# SPin.net
KiCad netlist of a schematic drawn in EAGLE
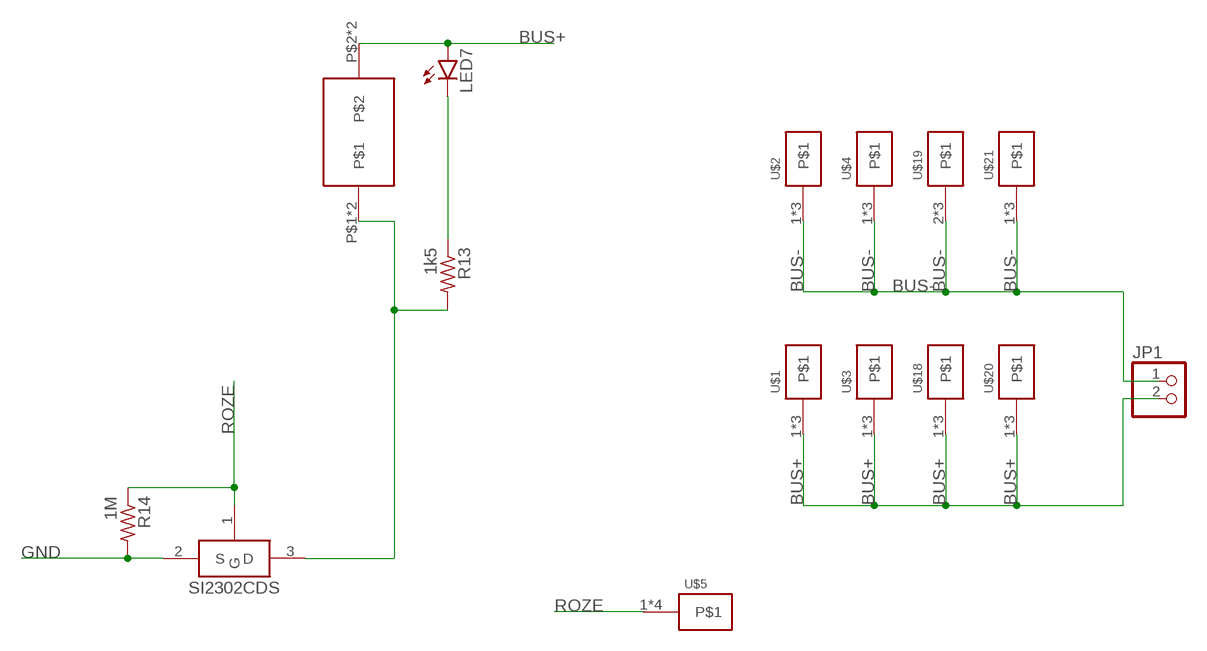
[diagram p0: schematic, sheet 1]

(export (version "E")
  (design (tool "Eeschema 10.0.6"))
  (components
    (comp (ref "JP1")
      (value "PINHD-1X2")
      (footprint "eagle-import:1X02")
      (libsource (lib "eagle-import") (part "PINHD-1X2"))
    )
    (comp (ref "LED7")
      (value "LEDCHIPLED_0603")
      (footprint "eagle-import:CHIPLED_0603")
      (libsource (lib "eagle-import") (part "LEDCHIPLED_0603"))
    )
    (comp (ref "R13")
      (value "1k5")
      (footprint "eagle-import:R0603")
      (libsource (lib "eagle-import") (part "R-US_R0603"))
    )
    (comp (ref "R14")
      (value "1M")
      (footprint "eagle-import:R0603")
      (libsource (lib "eagle-import") (part "R-US_R0603"))
    )
    (comp (ref "U$1")
      (value "KCONNECT3")
      (footprint "eagle-import:KCONNECT-3")
      (libsource (lib "eagle-import") (part "KCONNECT3"))
    )
    (comp (ref "U$2")
      (value "KCONNECT3")
      (footprint "eagle-import:KCONNECT-3")
      (libsource (lib "eagle-import") (part "KCONNECT3"))
    )
    (comp (ref "U$3")
      (value "KCONNECT4")
      (footprint "eagle-import:KCONNECT-4")
      (libsource (lib "eagle-import") (part "KCONNECT4"))
    )
    (comp (ref "U$4")
      (value "KCONNECT4")
      (footprint "eagle-import:KCONNECT-4")
      (libsource (lib "eagle-import") (part "KCONNECT4"))
    )
    (comp (ref "U$5")
      (value "KCONNECTQUAD-")
      (footprint "eagle-import:KCONNECT-_QUAD")
      (libsource (lib "eagle-import") (part "KCONNECTQUAD-"))
    )
    (comp (ref "U$6")
      (value "GRAFITGRAFIT4_2")
      (footprint "eagle-import:GRAFIT4_2")
      (libsource (lib "eagle-import") (part "GRAFITGRAFIT4_2"))
    )
    (comp (ref "U$13")
      (value "SI2302CDS")
      (footprint "eagle-import:SOT23-3")
      (libsource (lib "eagle-import") (part "SI2302CDS"))
    )
    (comp (ref "U$18")
      (value "KCONNECT4")
      (footprint "eagle-import:KCONNECT-4")
      (libsource (lib "eagle-import") (part "KCONNECT4"))
    )
    (comp (ref "U$19")
      (value "KCONNECT1")
      (footprint "eagle-import:KCONNECT-1")
      (libsource (lib "eagle-import") (part "KCONNECT1"))
    )
    (comp (ref "U$20")
      (value "KCONNECT3")
      (footprint "eagle-import:KCONNECT-3")
      (libsource (lib "eagle-import") (part "KCONNECT3"))
    )
    (comp (ref "U$21")
      (value "KCONNECT3")
      (footprint "eagle-import:KCONNECT-3")
      (libsource (lib "eagle-import") (part "KCONNECT3"))
    )
  )
  (nets
    (net (code "1") (name "/BUS+") (class "Default")
      (node (ref "JP1") (pin "2") (pinfunction "2_2") (pintype "passive"))
      (node (ref "LED7") (pin "A") (pinfunction "A_A") (pintype "passive"))
      (node (ref "U$1") (pin "1") (pinfunction "P$1_1") (pintype "bidirectional"))
      (node (ref "U$1") (pin "2") (pinfunction "P$1_2") (pintype "bidirectional"))
      (node (ref "U$1") (pin "4") (pinfunction "P$1_4") (pintype "bidirectional"))
      (node (ref "U$18") (pin "1") (pinfunction "P$1_1") (pintype "bidirectional"))
      (node (ref "U$18") (pin "2") (pinfunction "P$1_2") (pintype "bidirectional"))
      (node (ref "U$18") (pin "3") (pinfunction "P$1_3") (pintype "bidirectional"))
      (node (ref "U$20") (pin "1") (pinfunction "P$1_1") (pintype "bidirectional"))
      (node (ref "U$20") (pin "2") (pinfunction "P$1_2") (pintype "bidirectional"))
      (node (ref "U$20") (pin "4") (pinfunction "P$1_4") (pintype "bidirectional"))
      (node (ref "U$3") (pin "1") (pinfunction "P$1_1") (pintype "bidirectional"))
      (node (ref "U$3") (pin "2") (pinfunction "P$1_2") (pintype "bidirectional"))
      (node (ref "U$3") (pin "3") (pinfunction "P$1_3") (pintype "bidirectional"))
      (node (ref "U$6") (pin "P$2") (pinfunction "P$2_P$2") (pintype "bidirectional"))
      (node (ref "U$6") (pin "P$5") (pinfunction "P$2_P$5") (pintype "bidirectional"))
    )
    (net (code "2") (name "/BUS-") (class "Default")
      (node (ref "JP1") (pin "1") (pinfunction "1_1") (pintype "passive"))
      (node (ref "U$19") (pin "2") (pinfunction "P$1_2") (pintype "bidirectional"))
      (node (ref "U$19") (pin "3") (pinfunction "P$1_3") (pintype "bidirectional"))
      (node (ref "U$19") (pin "4") (pinfunction "P$1_4") (pintype "bidirectional"))
      (node (ref "U$2") (pin "1") (pinfunction "P$1_1") (pintype "bidirectional"))
      (node (ref "U$2") (pin "2") (pinfunction "P$1_2") (pintype "bidirectional"))
      (node (ref "U$2") (pin "4") (pinfunction "P$1_4") (pintype "bidirectional"))
      (node (ref "U$21") (pin "1") (pinfunction "P$1_1") (pintype "bidirectional"))
      (node (ref "U$21") (pin "2") (pinfunction "P$1_2") (pintype "bidirectional"))
      (node (ref "U$21") (pin "4") (pinfunction "P$1_4") (pintype "bidirectional"))
      (node (ref "U$4") (pin "1") (pinfunction "P$1_1") (pintype "bidirectional"))
      (node (ref "U$4") (pin "2") (pinfunction "P$1_2") (pintype "bidirectional"))
      (node (ref "U$4") (pin "3") (pinfunction "P$1_3") (pintype "bidirectional"))
    )
    (net (code "3") (name "/GND") (class "Default")
      (node (ref "R14") (pin "2") (pinfunction "2_2") (pintype "passive"))
      (node (ref "U$13") (pin "2") (pinfunction "S_2") (pintype "bidirectional"))
    )
    (net (code "4") (name "/ROZE") (class "Default")
      (node (ref "R14") (pin "1") (pinfunction "1_1") (pintype "passive"))
      (node (ref "U$13") (pin "1") (pinfunction "G_1") (pintype "bidirectional"))
      (node (ref "U$5") (pin "1") (pinfunction "P$1_1") (pintype "bidirectional"))
      (node (ref "U$5") (pin "2") (pinfunction "P$1_2") (pintype "bidirectional"))
      (node (ref "U$5") (pin "3") (pinfunction "P$1_3") (pintype "bidirectional"))
      (node (ref "U$5") (pin "4") (pinfunction "P$1_4") (pintype "bidirectional"))
    )
    (net (code "5") (name "Net-(LED7-PadC)") (class "Default")
      (node (ref "LED7") (pin "C") (pinfunction "C_C") (pintype "passive"))
      (node (ref "R13") (pin "1") (pinfunction "1_1") (pintype "passive"))
    )
    (net (code "6") (name "Net-(U$13-D)") (class "Default")
      (node (ref "R13") (pin "2") (pinfunction "2_2") (pintype "passive"))
      (node (ref "U$13") (pin "3") (pinfunction "D_3") (pintype "bidirectional"))
      (node (ref "U$6") (pin "P$1") (pinfunction "P$1_P$1") (pintype "bidirectional"))
      (node (ref "U$6") (pin "P$4") (pinfunction "P$1_P$4") (pintype "bidirectional"))
    )
  )
)
